# LVDS_repeater.net
KiCad netlist of a schematic drawn in Altium Designer
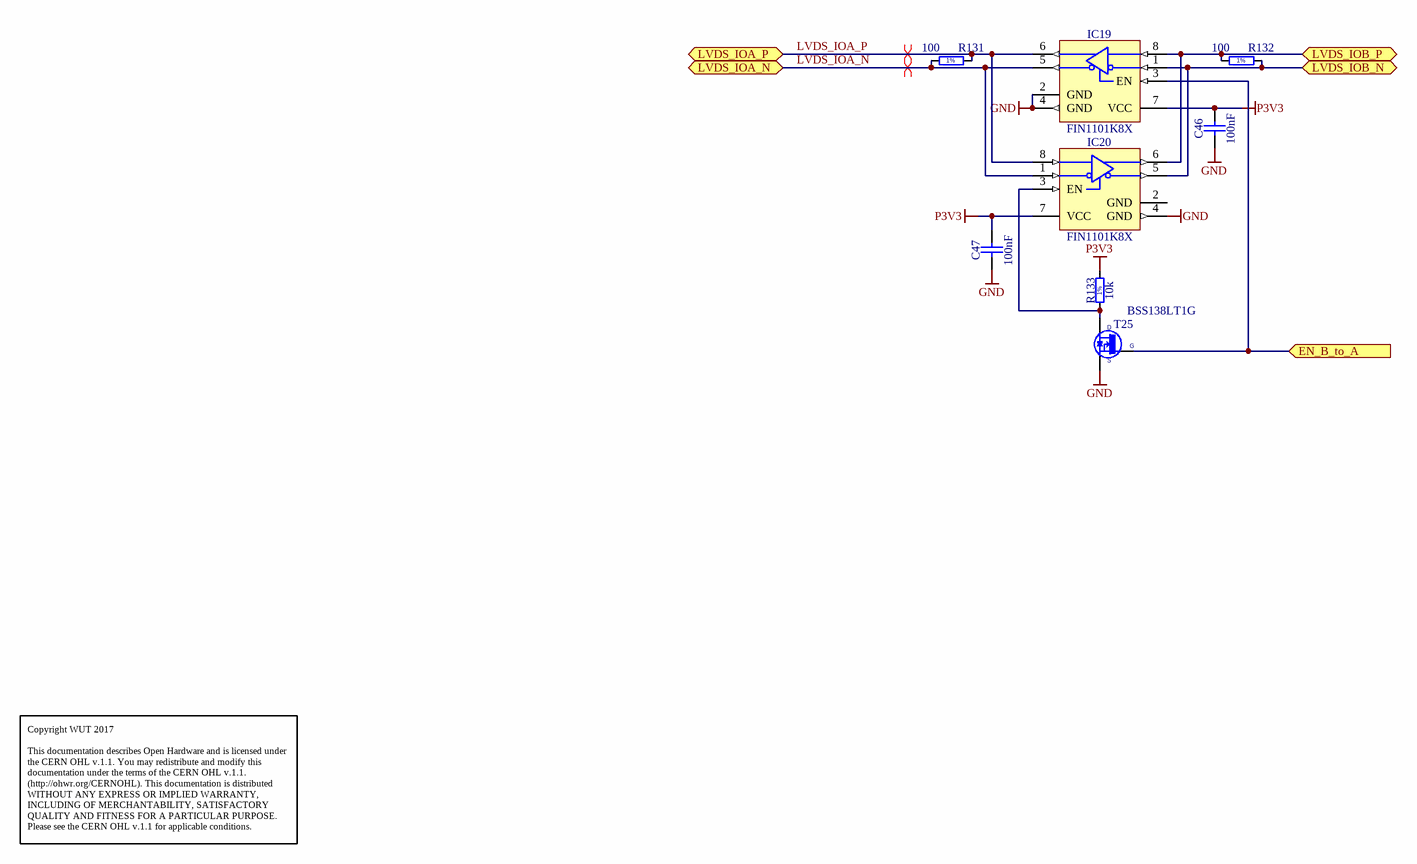
[diagram p0: LVDS_repeater.SchDoc]

(export (version "E")
  (design (tool "Eeschema 10.0.6"))
  (components
    (comp (ref "C46")
      (value "100nF")
      (footprint "CAPC1005X55N")
      (description "Non-polarised capacitor")
      (fields
        (field (name "PART NUMBER") "CC0402_100NF_16V_10%_X5R")
        (field (name "VOLTAGE") "16V")
        (field (name "AUTHOR") "CERN DEM JLC")
      )
      (libsource (lib "Capacitors") (part "Capacitor - non polarized"))
    )
    (comp (ref "C47")
      (value "100nF")
      (footprint "CAPC1005X55N")
      (description "Non-polarised capacitor")
      (fields
        (field (name "PART NUMBER") "CC0402_100NF_16V_10%_X5R")
        (field (name "VOLTAGE") "16V")
        (field (name "AUTHOR") "CERN DEM JLC")
      )
      (libsource (lib "Capacitors") (part "Capacitor - non polarized"))
    )
    (comp (ref "IC19")
      (value "FIN1101K8X")
      (footprint "SOP50P310X90-8N")
      (description "LVDS Single Port High Speed Repeater")
      (fields (field (name "MANUFACTURER") "FAIRCHILD SEMICONDUCTOR") (field (name "AUTHOR") "CERN DEM JLC"))
      (libsource (lib "") (part "FIN1101K8X_1"))
    )
    (comp (ref "IC20")
      (value "FIN1101K8X")
      (footprint "SOP50P310X90-8N")
      (description "LVDS Single Port High Speed Repeater")
      (fields (field (name "MANUFACTURER") "FAIRCHILD SEMICONDUCTOR") (field (name "AUTHOR") "CERN DEM JLC"))
      (libsource (lib "ICs And Semiconductors") (part "FIN1101K8X"))
    )
    (comp (ref "R131")
      (value "100")
      (footprint "RESC1005X40N")
      (description "Resistor - 1%")
      (fields
        (field (name "PART NUMBER") "R0402_100R_1%_0.1W_100PPM")
        (field (name "POWER") "0.1W")
        (field (name "AUTHOR") "CERN DEM JLC")
      )
      (libsource (lib "Resistors") (part "Resistor - 1%"))
    )
    (comp (ref "R132")
      (value "100")
      (footprint "RESC1005X40N")
      (description "Resistor - 1%")
      (fields
        (field (name "PART NUMBER") "R0402_100R_1%_0.1W_100PPM")
        (field (name "POWER") "0.1W")
        (field (name "AUTHOR") "CERN DEM JLC")
      )
      (libsource (lib "Resistors") (part "Resistor - 1%"))
    )
    (comp (ref "R133")
      (value "10k")
      (footprint "RESC1005X40N")
      (description "Resistor - 1%")
      (fields
        (field (name "PART NUMBER") "R0402_10K_1%_0.0625W_100PPM")
        (field (name "POWER") "0.0625W")
        (field (name "AUTHOR") "CERN DEM JLC")
      )
      (libsource (lib "Resistors") (part "Resistor - 1%"))
    )
    (comp (ref "T25")
      (value "BSS138LT1G")
      (footprint "SOT95P240X110-3N")
      (description "N-CHANNEL MOSFET WITH DIODE")
      (fields (field (name "MANUFACTURER") "ON SEMICONDUCTOR") (field (name "AUTHOR") "CERN DEM JLC"))
      (libsource (lib "ICs And Semiconductors") (part "N-MOSFET-D 1G 2S 3D"))
    )
  )
  (nets
    (net (code "1") (name "/EN_B_to_A") (class "Default")
      (node (ref "IC19") (pin "3") (pinfunction "EN_3") (pintype "input"))
      (node (ref "T25") (pin "1") (pinfunction "G_1") (pintype "passive"))
    )
    (net (code "2") (name "/LVDS_IOA_N") (class "Default")
      (node (ref "IC19") (pin "5") (pinfunction "DOUT-_5") (pintype "output"))
      (node (ref "IC20") (pin "1") (pinfunction "RIN-_1") (pintype "input"))
      (node (ref "R131") (pin "1") (pinfunction "1_1") (pintype "passive"))
    )
    (net (code "3") (name "/LVDS_IOA_P") (class "Default")
      (node (ref "IC19") (pin "6") (pinfunction "DOUT+_6") (pintype "output"))
      (node (ref "IC20") (pin "8") (pinfunction "RIN+_8") (pintype "input"))
      (node (ref "R131") (pin "2") (pinfunction "2_2") (pintype "passive"))
    )
    (net (code "4") (name "/LVDS_IOB_N") (class "Default")
      (node (ref "IC19") (pin "1") (pinfunction "RIN-_1") (pintype "input"))
      (node (ref "IC20") (pin "5") (pinfunction "DOUT-_5") (pintype "output"))
      (node (ref "R132") (pin "2") (pinfunction "2_2") (pintype "passive"))
    )
    (net (code "5") (name "/LVDS_IOB_P") (class "Default")
      (node (ref "IC19") (pin "8") (pinfunction "RIN+_8") (pintype "input"))
      (node (ref "IC20") (pin "6") (pinfunction "DOUT+_6") (pintype "output"))
      (node (ref "R132") (pin "1") (pinfunction "1_1") (pintype "passive"))
    )
    (net (code "6") (name "GND") (class "Default")
      (node (ref "C46") (pin "1") (pinfunction "1_1") (pintype "passive"))
      (node (ref "C47") (pin "1") (pinfunction "1_1") (pintype "passive"))
      (node (ref "IC19") (pin "2") (pinfunction "GND_2") (pintype "power_in"))
      (node (ref "IC19") (pin "4") (pinfunction "GND_4") (pintype "output"))
      (node (ref "IC20") (pin "4") (pinfunction "GND_4") (pintype "output"))
      (node (ref "T25") (pin "2") (pinfunction "S_2") (pintype "passive"))
    )
    (net (code "7") (name "Net-(IC20-EN)") (class "Default")
      (node (ref "IC20") (pin "3") (pinfunction "EN_3") (pintype "input"))
      (node (ref "R133") (pin "1") (pinfunction "1_1") (pintype "passive"))
      (node (ref "T25") (pin "3") (pinfunction "D_3") (pintype "passive"))
    )
    (net (code "8") (name "P3V3") (class "Default")
      (node (ref "C46") (pin "2") (pinfunction "2_2") (pintype "passive"))
      (node (ref "C47") (pin "2") (pinfunction "2_2") (pintype "passive"))
      (node (ref "IC19") (pin "7") (pinfunction "VCC_7") (pintype "power_in"))
      (node (ref "IC20") (pin "7") (pinfunction "VCC_7") (pintype "power_in"))
      (node (ref "R133") (pin "2") (pinfunction "2_2") (pintype "passive"))
    )
    (net (code "9") (name "unconnected-(IC20-GND-Pad2)") (class "Default")
      (node (ref "IC20") (pin "2") (pinfunction "GND_2") (pintype "power_in"))
    )
  )
)
